# out_drv.net
KiCad netlist of a schematic drawn in Altium Designer
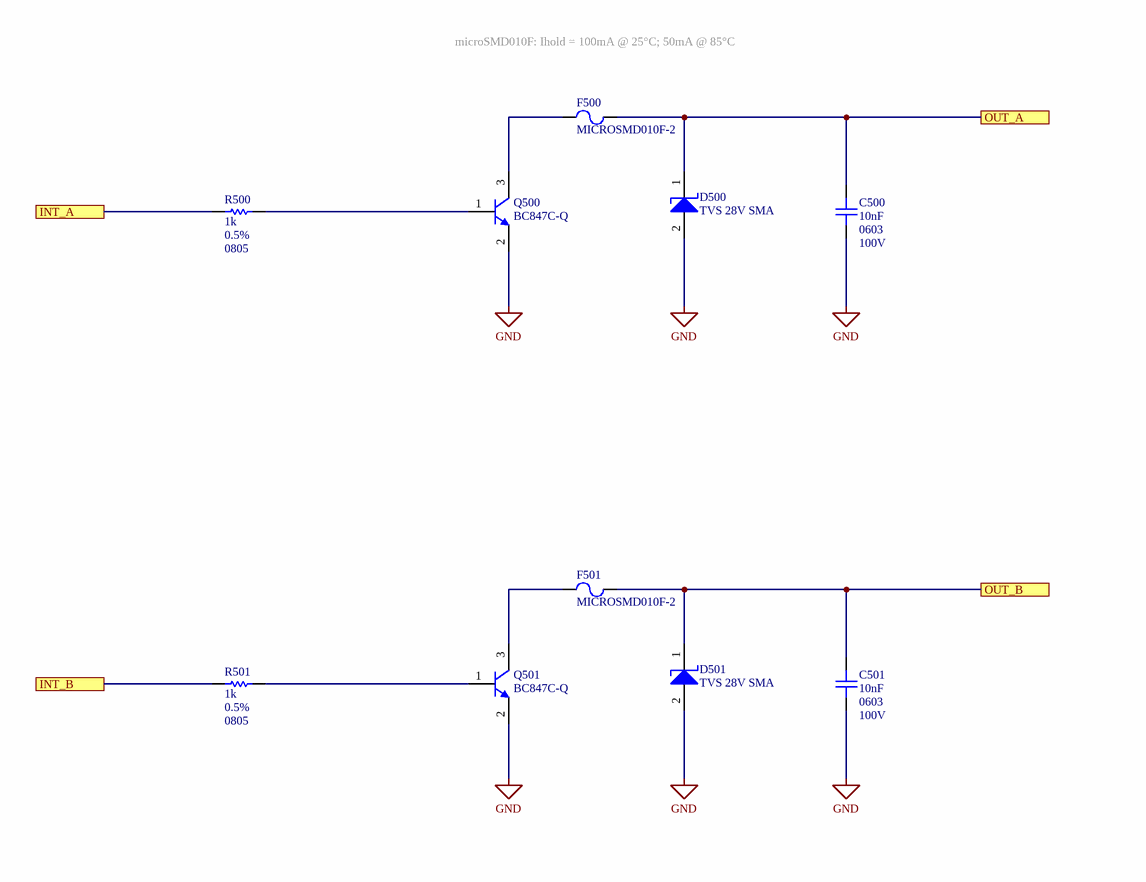
[diagram p0: out_drv.SchDoc, left]

(export (version "E")
  (design (tool "Eeschema 10.0.6"))
  (components
    (comp (ref "C500")
      (value "10nF")
      (footprint "CER0603")
      (description "MLCC Automotive, 10nF, 0603, 100V, 10%, X7R")
      (fields
        (field (name "CASE/PACKAGE") "0603")
        (field (name "OP VOLTAGE") "100V")
        (field (name "TOLERANCE") "10%")
      )
      (libsource (lib "PMP_CapsDB") (part "CapCer_SMD_2"))
    )
    (comp (ref "C501")
      (value "10nF")
      (footprint "CER0603")
      (description "MLCC Automotive, 10nF, 0603, 100V, 10%, X7R")
      (fields
        (field (name "CASE/PACKAGE") "0603")
        (field (name "OP VOLTAGE") "100V")
        (field (name "TOLERANCE") "10%")
      )
      (libsource (lib "PMP_CapsDB") (part "CapCer_SMD_2"))
    )
    (comp (ref "D500")
      (value "TVS 28V SMA")
      (footprint "DO-214AC_SMA")
      (description "TVS Uniir 28V SMA")
      (fields (field (name "Comment") "SMD/PTH TVS Unidirectional Diode"))
      (libsource (lib "Pmp_DiscretesDB") (part "TVS_2_Unidirectional"))
    )
    (comp (ref "D501")
      (value "TVS 28V SMA")
      (footprint "DO-214AC_SMA")
      (description "TVS Uniir 28V SMA")
      (fields (field (name "Comment") "SMD/PTH TVS Unidirectional Diode"))
      (libsource (lib "Pmp_DiscretesDB") (part "TVS_2_Unidirectional"))
    )
    (comp (ref "F500")
      (value "MICROSMD010F-2")
      (footprint "PTCC3226X08N")
      (description "Resettable Fuse PPTC, 100mA Hold, 250mA Trip, 2.1R min, 30V")
      (fields (field (name "Comment") "Fuse_PTCRes"))
      (libsource (lib "PMP_CirProtection") (part "FuseRes"))
    )
    (comp (ref "F501")
      (value "MICROSMD010F-2")
      (footprint "PTCC3226X08N")
      (description "Resettable Fuse PPTC, 100mA Hold, 250mA Trip, 2.1R min, 30V")
      (fields (field (name "Comment") "Fuse_PTCRes"))
      (libsource (lib "PMP_CirProtection") (part "FuseRes"))
    )
    (comp (ref "Q500")
      (value "BC847C-Q")
      (footprint "SOT95P230X110-3N")
      (description "NPN general purpose transistors")
      (fields (field (name "Comment") "NPN Transistor SMD"))
      (libsource (lib "Pmp_DiscretesDB") (part "TRANS_SMD_3_NPN_BEC"))
    )
    (comp (ref "Q501")
      (value "BC847C-Q")
      (footprint "SOT95P230X110-3N")
      (description "NPN general purpose transistors")
      (fields (field (name "Comment") "NPN Transistor SMD"))
      (libsource (lib "Pmp_DiscretesDB") (part "TRANS_SMD_3_NPN_BEC"))
    )
    (comp (ref "R500")
      (value "1k")
      (footprint "Res0603")
      (description "Thick Film SM Chip Resistors, 1K, 0805, ±0.5%, 1/2W")
      (fields
        (field (name "TOLERANCE") "0.5%")
        (field (name "CASE/PACKAGE") "0805")
        (field (name "POWER") "500mW")
        (field (name "Comment") "SMD Resistor")
      )
      (libsource (lib "PMP_ResDB") (part "Res_SMD_2"))
    )
    (comp (ref "R501")
      (value "1k")
      (footprint "Res0603")
      (description "Thick Film SM Chip Resistors, 1K, 0805, ±0.5%, 1/2W")
      (fields
        (field (name "TOLERANCE") "0.5%")
        (field (name "CASE/PACKAGE") "0805")
        (field (name "POWER") "500mW")
        (field (name "Comment") "SMD Resistor")
      )
      (libsource (lib "PMP_ResDB") (part "Res_SMD_2"))
    )
  )
  (nets
    (net (code "1") (name "/INT_A") (class "Default")
      (node (ref "R500") (pin "1") (pinfunction "1_1") (pintype "passive"))
    )
    (net (code "2") (name "/INT_B") (class "Default")
      (node (ref "R501") (pin "1") (pinfunction "1_1") (pintype "passive"))
    )
    (net (code "3") (name "/OUT_A") (class "Default")
      (node (ref "C500") (pin "1") (pinfunction "1_1") (pintype "passive"))
      (node (ref "D500") (pin "1") (pinfunction "K_1") (pintype "passive"))
      (node (ref "F500") (pin "2") (pinfunction "2_2") (pintype "passive"))
    )
    (net (code "4") (name "/OUT_B") (class "Default")
      (node (ref "C501") (pin "1") (pinfunction "1_1") (pintype "passive"))
      (node (ref "D501") (pin "1") (pinfunction "K_1") (pintype "passive"))
      (node (ref "F501") (pin "2") (pinfunction "2_2") (pintype "passive"))
    )
    (net (code "5") (name "GND") (class "Default")
      (node (ref "C500") (pin "2") (pinfunction "2_2") (pintype "passive"))
      (node (ref "C501") (pin "2") (pinfunction "2_2") (pintype "passive"))
      (node (ref "D500") (pin "2") (pinfunction "A_2") (pintype "passive"))
      (node (ref "D501") (pin "2") (pinfunction "A_2") (pintype "passive"))
      (node (ref "Q500") (pin "2") (pinfunction "E_2") (pintype "passive"))
      (node (ref "Q501") (pin "2") (pinfunction "E_2") (pintype "passive"))
    )
    (net (code "6") (name "Net-(Q500-B)") (class "Default")
      (node (ref "Q500") (pin "1") (pinfunction "B_1") (pintype "passive"))
      (node (ref "R500") (pin "2") (pinfunction "2_2") (pintype "passive"))
    )
    (net (code "7") (name "Net-(Q500-C)") (class "Default")
      (node (ref "F500") (pin "1") (pinfunction "1_1") (pintype "passive"))
      (node (ref "Q500") (pin "3") (pinfunction "C_3") (pintype "passive"))
    )
    (net (code "8") (name "Net-(Q501-B)") (class "Default")
      (node (ref "Q501") (pin "1") (pinfunction "B_1") (pintype "passive"))
      (node (ref "R501") (pin "2") (pinfunction "2_2") (pintype "passive"))
    )
    (net (code "9") (name "Net-(Q501-C)") (class "Default")
      (node (ref "F501") (pin "1") (pinfunction "1_1") (pintype "passive"))
      (node (ref "Q501") (pin "3") (pinfunction "C_3") (pintype "passive"))
    )
  )
)
